# ramu.net
KiCad netlist of a schematic drawn in EasyEDA
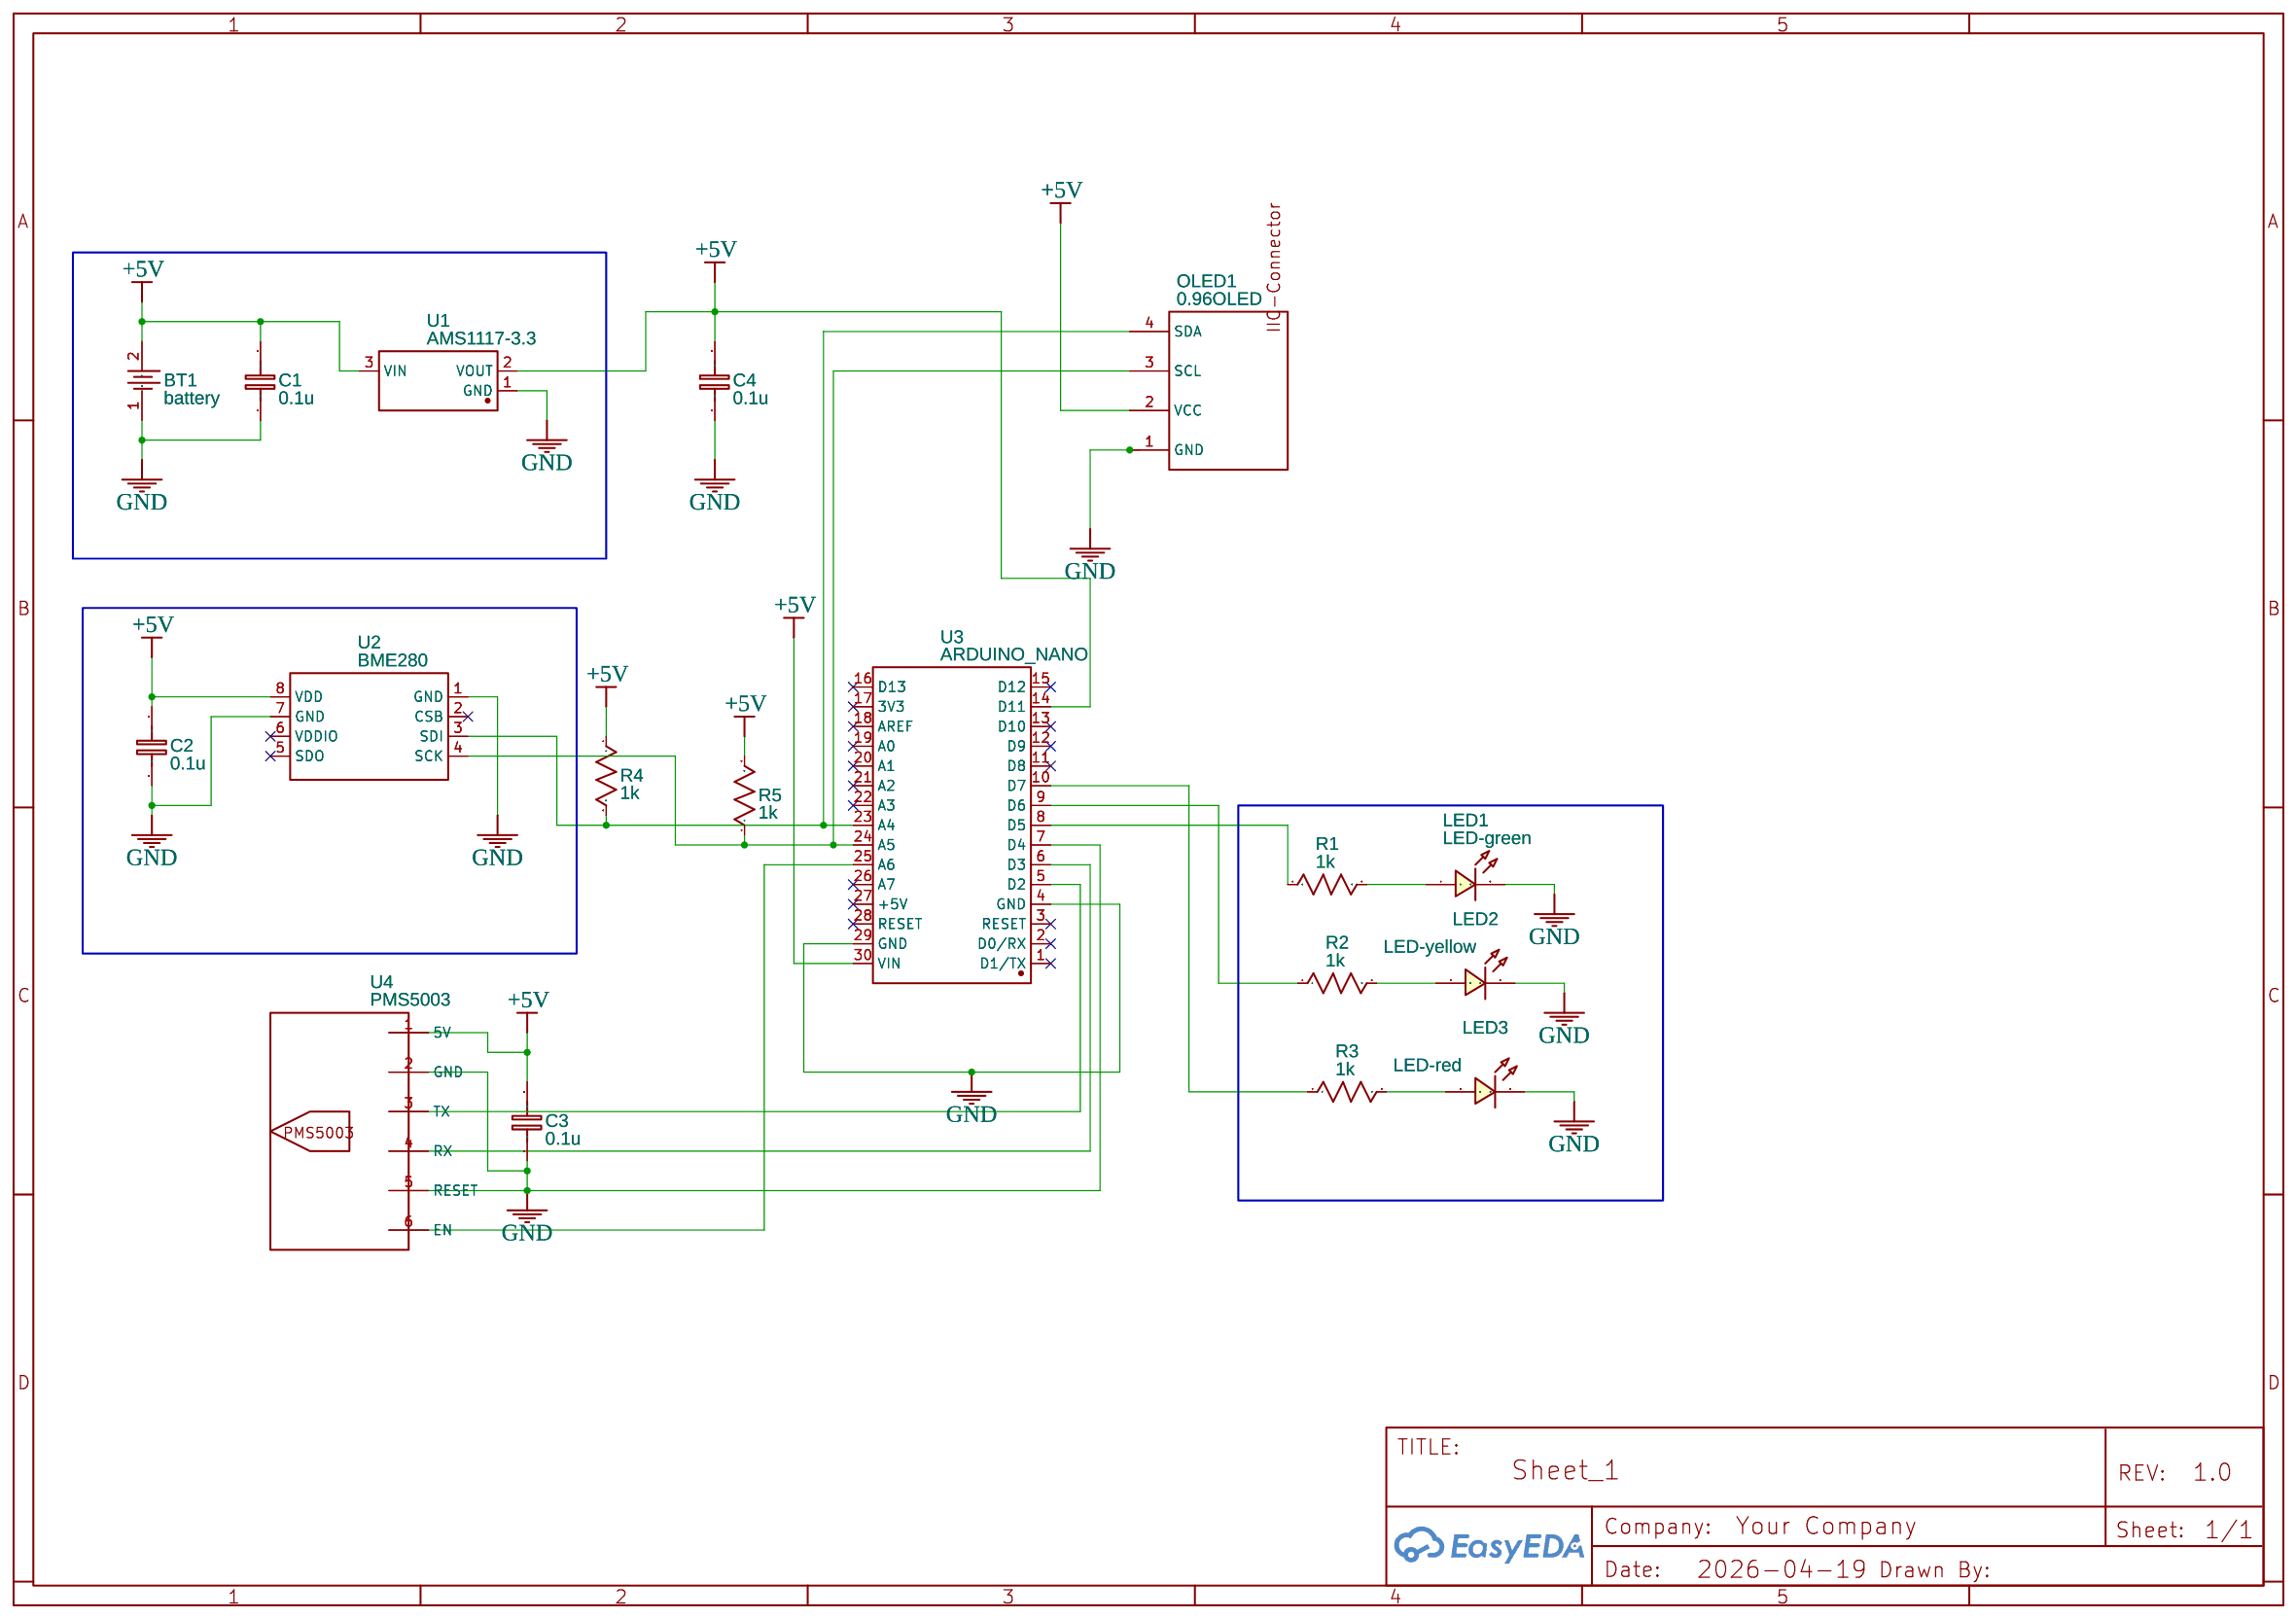
[diagram p0: schematic sheet]

(export (version "E")
  (design (tool "Eeschema 10.0.6"))
  (components
    (comp (ref "BT1")
      (value "battery")
      (fields
        (field (name "Manufacturer Part") "BH-18650-B1BA002")
        (field (name "Manufacturer") "MYOUNG(美阳)")
      )
      (libsource (lib "") (part "BH-18650-B1BA002"))
    )
    (comp (ref "C1") (value "0.1u") (libsource (lib "") (part "C_0603_EU_1")))
    (comp (ref "C2") (value "0.1u") (libsource (lib "") (part "C_0603_EU_2")))
    (comp (ref "C3") (value "0.1u") (libsource (lib "") (part "C_0603_EU")))
    (comp (ref "C4") (value "0.1u") (libsource (lib "") (part "C_0603_EU_1")))
    (comp (ref "LED1")
      (value "LED-green")
      (fields
        (field (name "Manufacturer Part") "19-217/R6C-AL1M2VY/3T")
        (field (name "Manufacturer") "EVERLIGHT(台湾亿光)")
      )
      (libsource (lib "") (part "LED-0603_R"))
    )
    (comp (ref "LED2")
      (value "LED-yellow")
      (fields
        (field (name "Manufacturer Part") "19-217/R6C-AL1M2VY/3T")
        (field (name "Manufacturer") "EVERLIGHT(台湾亿光)")
      )
      (libsource (lib "") (part "LED-0603_R"))
    )
    (comp (ref "LED3")
      (value "LED-red")
      (fields
        (field (name "Manufacturer Part") "19-217/R6C-AL1M2VY/3T")
        (field (name "Manufacturer") "EVERLIGHT(台湾亿光)")
      )
      (libsource (lib "") (part "LED-0603_R"))
    )
    (comp (ref "OLED1")
      (value "0.96OLED")
      (fields (field (name "Manufacturer Part") "0.96OLED_4P_MODULE_JX"))
      (libsource (lib "") (part "0.96OLED_4P_MODULE_JX"))
    )
    (comp (ref "R1") (value "1k") (libsource (lib "") (part "R_0603_US")))
    (comp (ref "R2") (value "1k") (libsource (lib "") (part "R_0603_US")))
    (comp (ref "R3") (value "1k") (libsource (lib "") (part "R_0603_US")))
    (comp (ref "R4") (value "1k") (libsource (lib "") (part "R_0603_US_2")))
    (comp (ref "R5") (value "1k") (libsource (lib "") (part "R_0603_US_1")))
    (comp (ref "U1")
      (value "AMS1117-3.3")
      (fields (field (name "Manufacturer Part") "AMS1117-3.3S-EV"))
      (libsource (lib "") (part "AMS1117-3.3S-EV"))
    )
    (comp (ref "U2")
      (value "BME280")
      (fields (field (name "Manufacturer") "Bosch(博世)"))
      (libsource (lib "") (part "BME280"))
    )
    (comp (ref "U3") (value "ARDUINO_NANO") (libsource (lib "") (part "ARDUINO_NANO")))
    (comp (ref "U4") (value "PMS5003") (libsource (lib "") (part "PMS5003")))
  )
  (nets
    (net (code "1") (name "+5V") (class "Default")
      (node (ref "BT1") (pin "2") (pinfunction "2_2") (pintype "input"))
      (node (ref "C1") (pin "2") (pinfunction "2_2") (pintype "unspecified"))
      (node (ref "C2") (pin "2") (pinfunction "2_2") (pintype "unspecified"))
      (node (ref "C3") (pin "2") (pinfunction "2_2") (pintype "unspecified"))
      (node (ref "C4") (pin "2") (pinfunction "2_2") (pintype "unspecified"))
      (node (ref "OLED1") (pin "2") (pinfunction "VCC_2") (pintype "unspecified"))
      (node (ref "R4") (pin "1") (pinfunction "1_1") (pintype "unspecified"))
      (node (ref "R5") (pin "2") (pinfunction "2_2") (pintype "unspecified"))
      (node (ref "U1") (pin "2") (pinfunction "VOUT_2") (pintype "unspecified"))
      (node (ref "U1") (pin "3") (pinfunction "VIN_3") (pintype "unspecified"))
      (node (ref "U2") (pin "8") (pinfunction "VDD_8") (pintype "unspecified"))
      (node (ref "U3") (pin "14") (pinfunction "D11_14") (pintype "unspecified"))
      (node (ref "U3") (pin "30") (pinfunction "VIN_30") (pintype "unspecified"))
      (node (ref "U4") (pin "1") (pinfunction "5V_1") (pintype "unspecified"))
    )
    (net (code "2") (name "GND") (class "Default")
      (node (ref "BT1") (pin "1") (pinfunction "1_1") (pintype "input"))
      (node (ref "C1") (pin "1") (pinfunction "1_1") (pintype "unspecified"))
      (node (ref "C2") (pin "1") (pinfunction "1_1") (pintype "unspecified"))
      (node (ref "C3") (pin "1") (pinfunction "1_1") (pintype "unspecified"))
      (node (ref "C4") (pin "1") (pinfunction "1_1") (pintype "unspecified"))
      (node (ref "LED1") (pin "2") (pinfunction "2_2") (pintype "unspecified"))
      (node (ref "LED2") (pin "2") (pinfunction "2_2") (pintype "unspecified"))
      (node (ref "LED3") (pin "2") (pinfunction "2_2") (pintype "unspecified"))
      (node (ref "OLED1") (pin "1") (pinfunction "GND_1") (pintype "unspecified"))
      (node (ref "U1") (pin "1") (pinfunction "GND_1") (pintype "unspecified"))
      (node (ref "U2") (pin "1") (pinfunction "GND_1") (pintype "unspecified"))
      (node (ref "U2") (pin "7") (pinfunction "GND_7") (pintype "unspecified"))
      (node (ref "U3") (pin "29") (pinfunction "GND_29") (pintype "unspecified"))
      (node (ref "U3") (pin "4") (pinfunction "GND_4") (pintype "unspecified"))
      (node (ref "U3") (pin "7") (pinfunction "D4_7") (pintype "unspecified"))
      (node (ref "U4") (pin "2") (pinfunction "GND_2") (pintype "unspecified"))
      (node (ref "U4") (pin "5") (pinfunction "RESET_5") (pintype "unspecified"))
    )
    (net (code "3") (name "Net-(LED1-Pad1)") (class "Default")
      (node (ref "LED1") (pin "1") (pinfunction "1_1") (pintype "unspecified"))
      (node (ref "R1") (pin "2") (pinfunction "2_2") (pintype "unspecified"))
    )
    (net (code "4") (name "Net-(LED2-Pad1)") (class "Default")
      (node (ref "LED2") (pin "1") (pinfunction "1_1") (pintype "unspecified"))
      (node (ref "R2") (pin "2") (pinfunction "2_2") (pintype "unspecified"))
    )
    (net (code "5") (name "Net-(LED3-Pad1)") (class "Default")
      (node (ref "LED3") (pin "1") (pinfunction "1_1") (pintype "unspecified"))
      (node (ref "R3") (pin "2") (pinfunction "2_2") (pintype "unspecified"))
    )
    (net (code "6") (name "Net-(OLED1-SCL)") (class "Default")
      (node (ref "OLED1") (pin "3") (pinfunction "SCL_3") (pintype "unspecified"))
      (node (ref "R5") (pin "1") (pinfunction "1_1") (pintype "unspecified"))
      (node (ref "U2") (pin "4") (pinfunction "SCK_4") (pintype "unspecified"))
      (node (ref "U3") (pin "24") (pinfunction "A5_24") (pintype "unspecified"))
    )
    (net (code "7") (name "Net-(OLED1-SDA)") (class "Default")
      (node (ref "OLED1") (pin "4") (pinfunction "SDA_4") (pintype "unspecified"))
      (node (ref "R4") (pin "2") (pinfunction "2_2") (pintype "unspecified"))
      (node (ref "U2") (pin "3") (pinfunction "SDI_3") (pintype "unspecified"))
      (node (ref "U3") (pin "23") (pinfunction "A4_23") (pintype "unspecified"))
    )
    (net (code "8") (name "Net-(U3-A6)") (class "Default")
      (node (ref "U3") (pin "25") (pinfunction "A6_25") (pintype "unspecified"))
      (node (ref "U4") (pin "6") (pinfunction "EN_6") (pintype "unspecified"))
    )
    (net (code "9") (name "Net-(U3-D2)") (class "Default")
      (node (ref "U3") (pin "5") (pinfunction "D2_5") (pintype "unspecified"))
      (node (ref "U4") (pin "3") (pinfunction "TX_3") (pintype "unspecified"))
    )
    (net (code "10") (name "Net-(U3-D3)") (class "Default")
      (node (ref "U3") (pin "6") (pinfunction "D3_6") (pintype "unspecified"))
      (node (ref "U4") (pin "4") (pinfunction "RX_4") (pintype "unspecified"))
    )
    (net (code "11") (name "Net-(U3-D5)") (class "Default")
      (node (ref "R1") (pin "1") (pinfunction "1_1") (pintype "unspecified"))
      (node (ref "U3") (pin "8") (pinfunction "D5_8") (pintype "unspecified"))
    )
    (net (code "12") (name "Net-(U3-D6)") (class "Default")
      (node (ref "R2") (pin "1") (pinfunction "1_1") (pintype "unspecified"))
      (node (ref "U3") (pin "9") (pinfunction "D6_9") (pintype "unspecified"))
    )
    (net (code "13") (name "Net-(U3-D7)") (class "Default")
      (node (ref "R3") (pin "1") (pinfunction "1_1") (pintype "unspecified"))
      (node (ref "U3") (pin "10") (pinfunction "D7_10") (pintype "unspecified"))
    )
    (net (code "14") (name "unconnected-(U2-CSB-Pad2)") (class "Default")
      (node (ref "U2") (pin "2") (pinfunction "CSB_2") (pintype "unspecified+no_connect"))
    )
    (net (code "15") (name "unconnected-(U2-SDO-Pad5)") (class "Default")
      (node (ref "U2") (pin "5") (pinfunction "SDO_5") (pintype "unspecified+no_connect"))
    )
    (net (code "16") (name "unconnected-(U2-VDDIO-Pad6)") (class "Default")
      (node (ref "U2") (pin "6") (pinfunction "VDDIO_6") (pintype "unspecified+no_connect"))
    )
    (net (code "17") (name "unconnected-(U3-+5V-Pad27)") (class "Default")
      (node (ref "U3") (pin "27") (pinfunction "+5V_27") (pintype "unspecified+no_connect"))
    )
    (net (code "18") (name "unconnected-(U3-3V3-Pad17)") (class "Default")
      (node (ref "U3") (pin "17") (pinfunction "3V3_17") (pintype "unspecified+no_connect"))
    )
    (net (code "19") (name "unconnected-(U3-A0-Pad19)") (class "Default")
      (node (ref "U3") (pin "19") (pinfunction "A0_19") (pintype "unspecified+no_connect"))
    )
    (net (code "20") (name "unconnected-(U3-A1-Pad20)") (class "Default")
      (node (ref "U3") (pin "20") (pinfunction "A1_20") (pintype "unspecified+no_connect"))
    )
    (net (code "21") (name "unconnected-(U3-A2-Pad21)") (class "Default")
      (node (ref "U3") (pin "21") (pinfunction "A2_21") (pintype "unspecified+no_connect"))
    )
    (net (code "22") (name "unconnected-(U3-A3-Pad22)") (class "Default")
      (node (ref "U3") (pin "22") (pinfunction "A3_22") (pintype "unspecified+no_connect"))
    )
    (net (code "23") (name "unconnected-(U3-A7-Pad26)") (class "Default")
      (node (ref "U3") (pin "26") (pinfunction "A7_26") (pintype "unspecified+no_connect"))
    )
    (net (code "24") (name "unconnected-(U3-AREF-Pad18)") (class "Default")
      (node (ref "U3") (pin "18") (pinfunction "AREF_18") (pintype "unspecified+no_connect"))
    )
    (net (code "25") (name "unconnected-(U3-D0{slash}RX-Pad2)") (class "Default")
      (node (ref "U3") (pin "2") (pinfunction "D0/RX_2") (pintype "unspecified+no_connect"))
    )
    (net (code "26") (name "unconnected-(U3-D1{slash}TX-Pad1)") (class "Default")
      (node (ref "U3") (pin "1") (pinfunction "D1/TX_1") (pintype "unspecified+no_connect"))
    )
    (net (code "27") (name "unconnected-(U3-D8-Pad11)") (class "Default")
      (node (ref "U3") (pin "11") (pinfunction "D8_11") (pintype "unspecified+no_connect"))
    )
    (net (code "28") (name "unconnected-(U3-D9-Pad12)") (class "Default")
      (node (ref "U3") (pin "12") (pinfunction "D9_12") (pintype "unspecified+no_connect"))
    )
    (net (code "29") (name "unconnected-(U3-D10-Pad13)") (class "Default")
      (node (ref "U3") (pin "13") (pinfunction "D10_13") (pintype "unspecified+no_connect"))
    )
    (net (code "30") (name "unconnected-(U3-D12-Pad15)") (class "Default")
      (node (ref "U3") (pin "15") (pinfunction "D12_15") (pintype "unspecified+no_connect"))
    )
    (net (code "31") (name "unconnected-(U3-D13-Pad16)") (class "Default")
      (node (ref "U3") (pin "16") (pinfunction "D13_16") (pintype "unspecified+no_connect"))
    )
    (net (code "32") (name "unconnected-(U3-RESET-Pad3)") (class "Default")
      (node (ref "U3") (pin "3") (pinfunction "RESET_3") (pintype "unspecified+no_connect"))
    )
    (net (code "33") (name "unconnected-(U3-RESET-Pad28)") (class "Default")
      (node (ref "U3") (pin "28") (pinfunction "RESET_28") (pintype "unspecified+no_connect"))
    )
  )
)
